# Esquematico1.net
KiCad netlist of a schematic drawn in Altium Designer
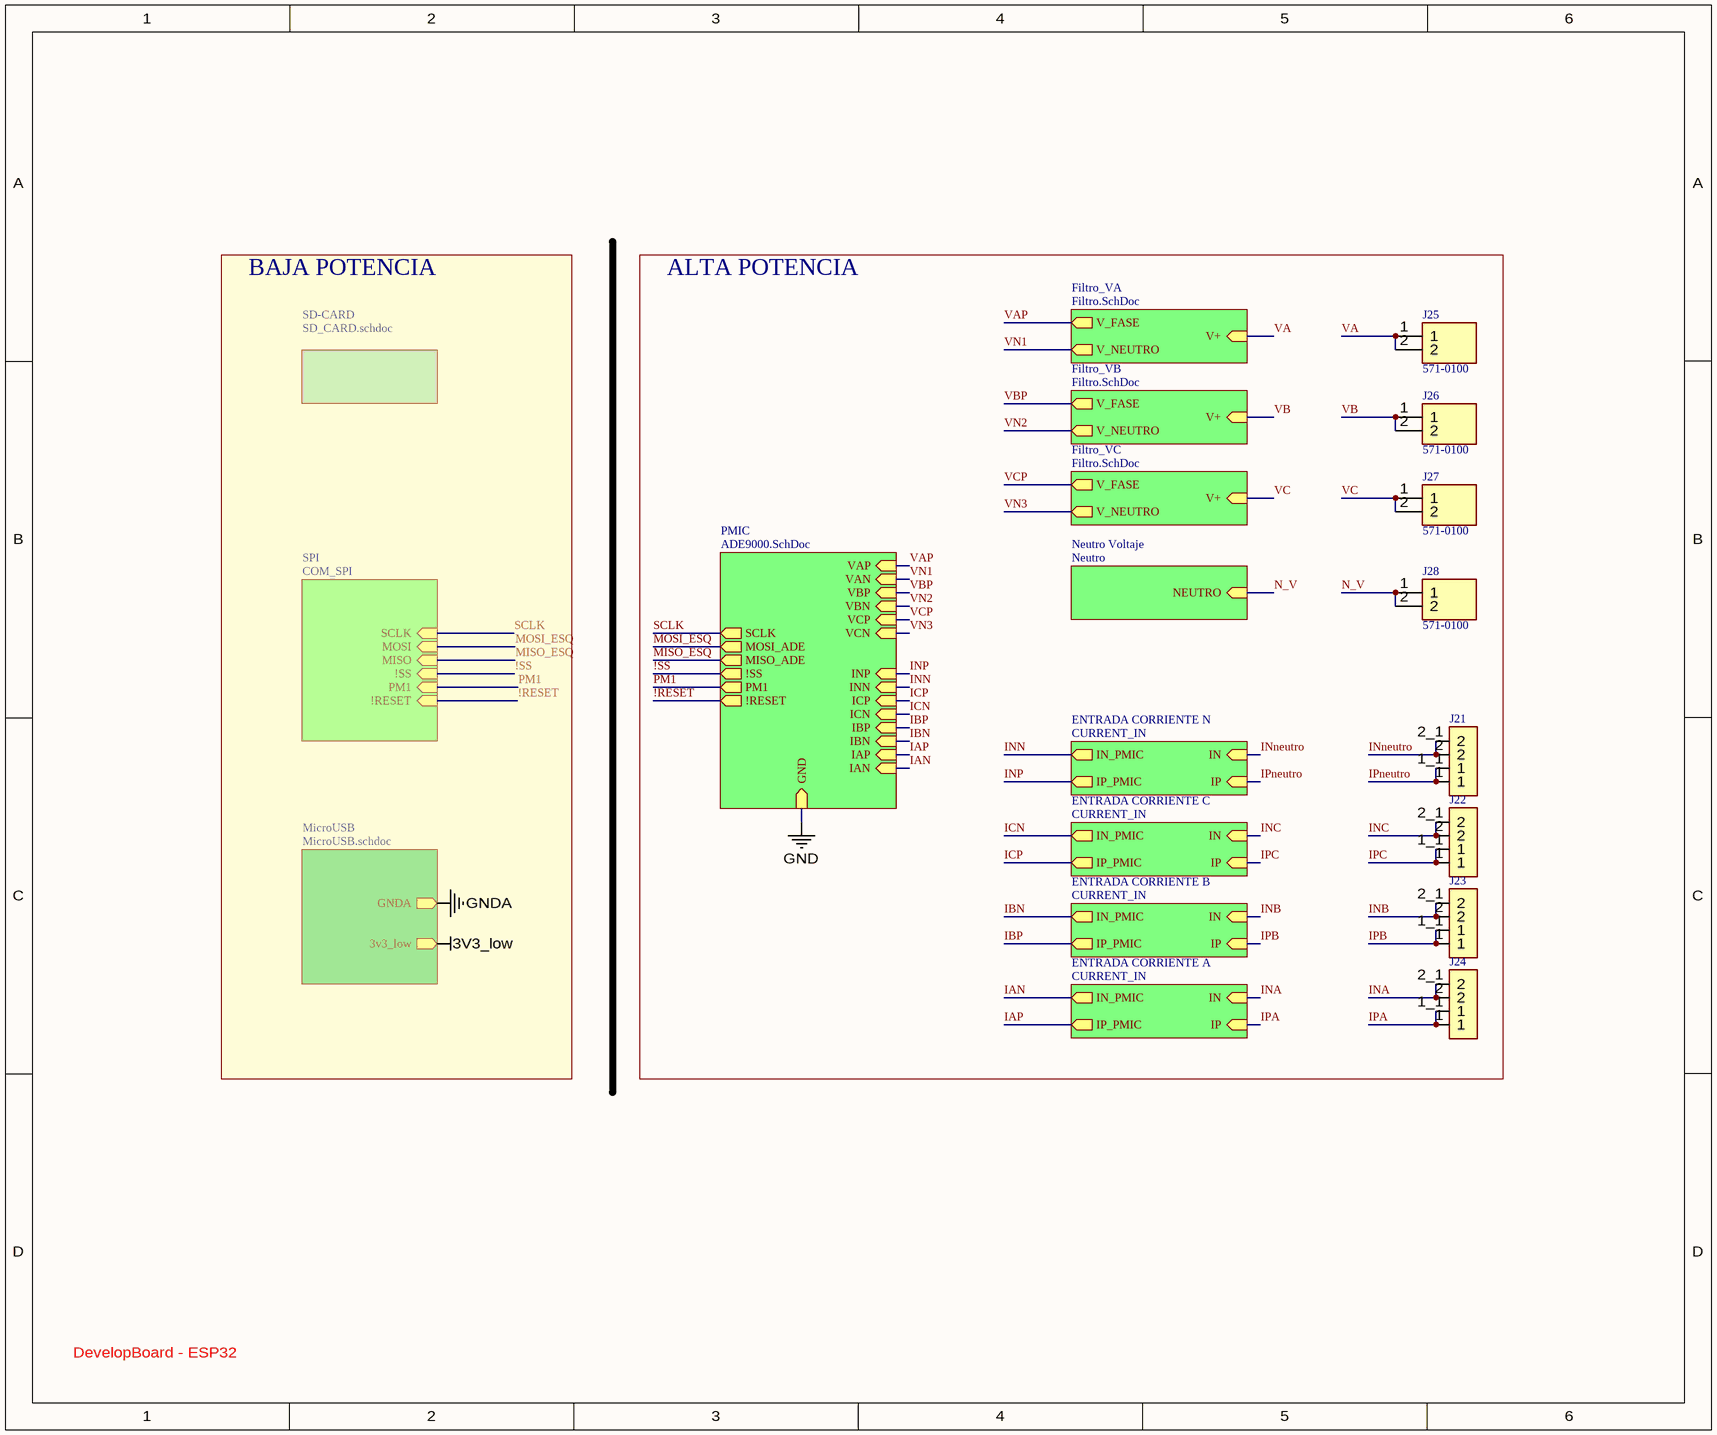
[diagram p0: Esquematico1.schdoc]

(export (version "E")
  (design (tool "Eeschema 10.0.6"))
  (components
    (comp (ref "J21")
      (value "2834082-1")
      (footprint "TE_2834082-1")
      (description "Conn PC Terminal Block 2 POS 5mm Solder ST Thru-Hole 20A/Contact Box/Carton")
      (fields (field (name "DIGI-KEY_PART_NUMBER") "A124223-ND") (field (name "MF") "TE Connectivity"))
      (libsource (lib "2834082-1") (part "2834082-1"))
    )
    (comp (ref "J22")
      (value "2834082-1")
      (footprint "TE_2834082-1")
      (description "Conn PC Terminal Block 2 POS 5mm Solder ST Thru-Hole 20A/Contact Box/Carton")
      (fields (field (name "DIGI-KEY_PART_NUMBER") "A124223-ND") (field (name "MF") "TE Connectivity"))
      (libsource (lib "2834082-1") (part "2834082-1"))
    )
    (comp (ref "J23")
      (value "2834082-1")
      (footprint "TE_2834082-1")
      (description "Conn PC Terminal Block 2 POS 5mm Solder ST Thru-Hole 20A/Contact Box/Carton")
      (fields (field (name "DIGI-KEY_PART_NUMBER") "A124223-ND") (field (name "MF") "TE Connectivity"))
      (libsource (lib "2834082-1") (part "2834082-1"))
    )
    (comp (ref "J24")
      (value "2834082-1")
      (footprint "TE_2834082-1")
      (description "Conn PC Terminal Block 2 POS 5mm Solder ST Thru-Hole 20A/Contact Box/Carton")
      (fields (field (name "DIGI-KEY_PART_NUMBER") "A124223-ND") (field (name "MF") "TE Connectivity"))
      (libsource (lib "2834082-1") (part "2834082-1"))
    )
    (comp (ref "J25")
      (value "571-0100")
      (footprint "SamacSys:5710100")
      (description "Connector")
      (fields (field (name "MOUSER PART NUMBER") "164-6218"))
      (libsource (lib "*") (part "571-0100"))
    )
    (comp (ref "J26")
      (value "571-0100")
      (footprint "SamacSys:5710100")
      (description "Connector")
      (fields (field (name "MOUSER PART NUMBER") "164-6218"))
      (libsource (lib "*") (part "571-0100"))
    )
    (comp (ref "J27")
      (value "571-0100")
      (footprint "SamacSys:5710100")
      (description "Connector")
      (fields (field (name "MOUSER PART NUMBER") "164-6218"))
      (libsource (lib "*") (part "571-0100"))
    )
    (comp (ref "J28")
      (value "571-0100")
      (footprint "SamacSys:5710100")
      (description "Connector")
      (fields (field (name "MOUSER PART NUMBER") "164-6218"))
      (libsource (lib "*") (part "571-0100"))
    )
  )
  (nets
    (net (code "9") (name "/INA") (class "Default")
      (node (ref "J24") (pin "2") (pinfunction "2_2") (pintype "passive"))
      (node (ref "J24") (pin "2_1") (pinfunction "2_2_1") (pintype "passive"))
    )
    (net (code "10") (name "/INB") (class "Default")
      (node (ref "J23") (pin "2") (pinfunction "2_2") (pintype "passive"))
      (node (ref "J23") (pin "2_1") (pinfunction "2_2_1") (pintype "passive"))
    )
    (net (code "11") (name "/INC") (class "Default")
      (node (ref "J22") (pin "2") (pinfunction "2_2") (pintype "passive"))
      (node (ref "J22") (pin "2_1") (pinfunction "2_2_1") (pintype "passive"))
    )
    (net (code "14") (name "/INneutro") (class "Default")
      (node (ref "J21") (pin "2") (pinfunction "2_2") (pintype "passive"))
      (node (ref "J21") (pin "2_1") (pinfunction "2_2_1") (pintype "passive"))
    )
    (net (code "15") (name "/IPA") (class "Default")
      (node (ref "J24") (pin "1") (pinfunction "1_1") (pintype "passive"))
      (node (ref "J24") (pin "1_1") (pinfunction "1_1_1") (pintype "passive"))
    )
    (net (code "16") (name "/IPB") (class "Default")
      (node (ref "J23") (pin "1") (pinfunction "1_1") (pintype "passive"))
      (node (ref "J23") (pin "1_1") (pinfunction "1_1_1") (pintype "passive"))
    )
    (net (code "17") (name "/IPC") (class "Default")
      (node (ref "J22") (pin "1") (pinfunction "1_1") (pintype "passive"))
      (node (ref "J22") (pin "1_1") (pinfunction "1_1_1") (pintype "passive"))
    )
    (net (code "18") (name "/IPneutro") (class "Default")
      (node (ref "J21") (pin "1") (pinfunction "1_1") (pintype "passive"))
      (node (ref "J21") (pin "1_1") (pinfunction "1_1_1") (pintype "passive"))
    )
    (net (code "21") (name "/N_V") (class "Default")
      (node (ref "J28") (pin "1") (pinfunction "1_1") (pintype "passive"))
      (node (ref "J28") (pin "2") (pinfunction "2_2") (pintype "passive"))
    )
    (net (code "24") (name "/VA") (class "Default")
      (node (ref "J25") (pin "1") (pinfunction "1_1") (pintype "passive"))
      (node (ref "J25") (pin "2") (pinfunction "2_2") (pintype "passive"))
    )
    (net (code "26") (name "/VB") (class "Default")
      (node (ref "J26") (pin "1") (pinfunction "1_1") (pintype "passive"))
      (node (ref "J26") (pin "2") (pinfunction "2_2") (pintype "passive"))
    )
    (net (code "28") (name "/VC") (class "Default")
      (node (ref "J27") (pin "1") (pinfunction "1_1") (pintype "passive"))
      (node (ref "J27") (pin "2") (pinfunction "2_2") (pintype "passive"))
    )
  )
)
